# Projeto_Lora.net
KiCad netlist of a schematic drawn in EAGLE
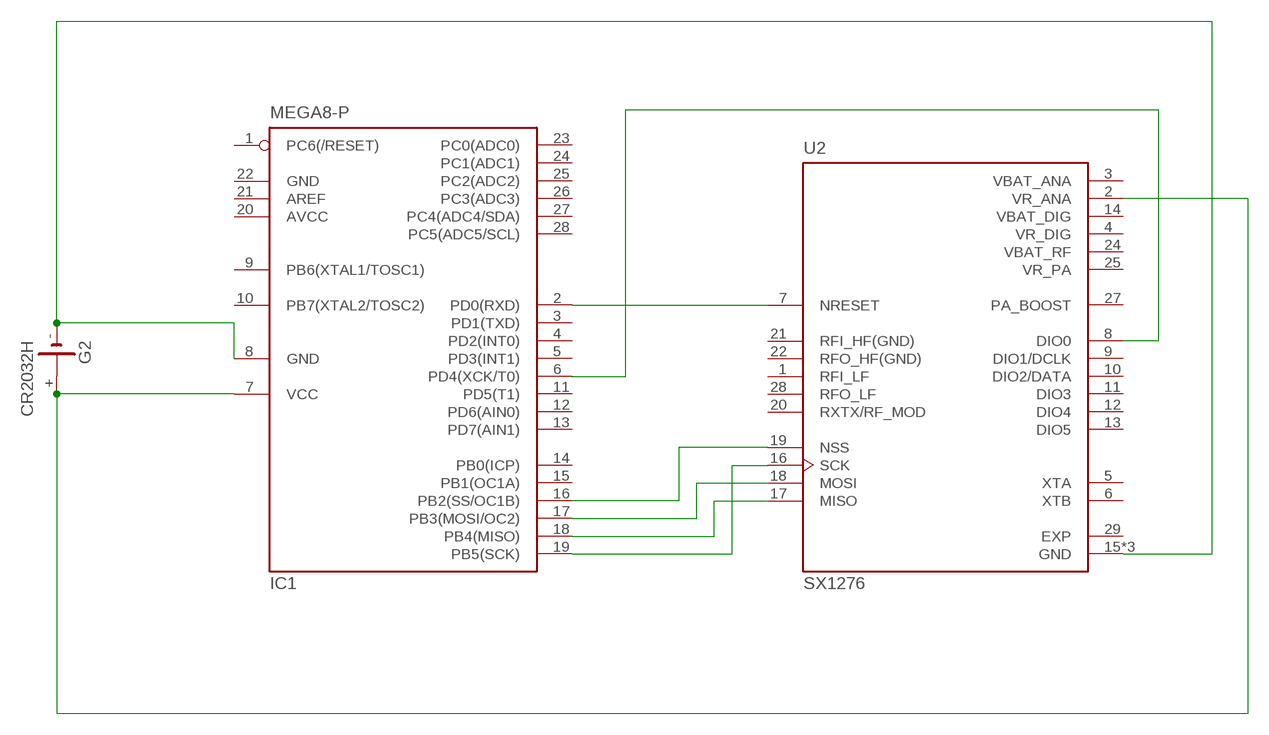
[diagram p0: schematic, sheet 1]

(export (version "E")
  (design (tool "Eeschema 10.0.6"))
  (components
    (comp (ref "G2")
      (value "CR2032H")
      (footprint "eagle-import:CR2032H")
      (libsource (lib "eagle-import") (part "CR2032H"))
    )
    (comp (ref "IC1")
      (value "MEGA8-P")
      (footprint "eagle-import:DIL28-3")
      (libsource (lib "eagle-import") (part "MEGA8-P"))
    )
    (comp (ref "U2")
      (value "SX1276")
      (footprint "eagle-import:QFN65P600X600X100-29N")
      (fields (field (name "MF") "Semtech Corporation"))
      (libsource (lib "eagle-import") (part "SX1276"))
    )
  )
  (nets
    (net (code "1") (name "/AVCC") (class "Default")
      (node (ref "IC1") (pin "20") (pinfunction "AVCC_20") (pintype "power_in"))
    )
    (net (code "2") (name "/EXP") (class "Default")
      (node (ref "U2") (pin "29") (pinfunction "EXP_29") (pintype "power_in"))
    )
    (net (code "3") (name "/GND") (class "Default")
      (node (ref "IC1") (pin "22") (pinfunction "GND_22") (pintype "power_in"))
    )
    (net (code "4") (name "/VBAT_ANA") (class "Default")
      (node (ref "U2") (pin "3") (pinfunction "VBAT_ANA_3") (pintype "power_in"))
    )
    (net (code "5") (name "/VBAT_DIG") (class "Default")
      (node (ref "U2") (pin "14") (pinfunction "VBAT_DIG_14") (pintype "power_in"))
    )
    (net (code "6") (name "/VBAT_RF") (class "Default")
      (node (ref "U2") (pin "24") (pinfunction "VBAT_RF_24") (pintype "power_in"))
    )
    (net (code "7") (name "/VR_DIG") (class "Default")
      (node (ref "U2") (pin "4") (pinfunction "VR_DIG_4") (pintype "power_in"))
    )
    (net (code "8") (name "/VR_PA") (class "Default")
      (node (ref "U2") (pin "25") (pinfunction "VR_PA_25") (pintype "power_in"))
    )
    (net (code "9") (name "Net-(G2-Pad-)") (class "Default")
      (node (ref "G2") (pin "-") (pinfunction "-_-") (pintype "passive"))
      (node (ref "IC1") (pin "8") (pinfunction "GND_8") (pintype "power_in"))
      (node (ref "U2") (pin "15") (pinfunction "GND_15") (pintype "power_in"))
      (node (ref "U2") (pin "23") (pinfunction "GND_23") (pintype "power_in"))
      (node (ref "U2") (pin "26") (pinfunction "GND_26") (pintype "power_in"))
    )
    (net (code "10") (name "Net-(IC1-PB2(SS{slash}OC1B))") (class "Default")
      (node (ref "IC1") (pin "16") (pinfunction "PB2(SS/OC1B)_16") (pintype "bidirectional"))
      (node (ref "U2") (pin "19") (pinfunction "NSS_19") (pintype "input"))
    )
    (net (code "11") (name "Net-(IC1-PB3(MOSI{slash}OC2))") (class "Default")
      (node (ref "IC1") (pin "17") (pinfunction "PB3(MOSI/OC2)_17") (pintype "bidirectional"))
      (node (ref "U2") (pin "18") (pinfunction "MOSI_18") (pintype "input"))
    )
    (net (code "12") (name "Net-(IC1-PB4(MISO))") (class "Default")
      (node (ref "IC1") (pin "18") (pinfunction "PB4(MISO)_18") (pintype "bidirectional"))
      (node (ref "U2") (pin "17") (pinfunction "MISO_17") (pintype "output"))
    )
    (net (code "13") (name "Net-(IC1-PB5(SCK))") (class "Default")
      (node (ref "IC1") (pin "19") (pinfunction "PB5(SCK)_19") (pintype "bidirectional"))
      (node (ref "U2") (pin "16") (pinfunction "SCK_16") (pintype "input"))
    )
    (net (code "14") (name "Net-(IC1-PD0(RXD))") (class "Default")
      (node (ref "IC1") (pin "2") (pinfunction "PD0(RXD)_2") (pintype "bidirectional"))
      (node (ref "U2") (pin "7") (pinfunction "NRESET_7") (pintype "bidirectional"))
    )
    (net (code "15") (name "Net-(IC1-PD4(XCK{slash}T0))") (class "Default")
      (node (ref "IC1") (pin "6") (pinfunction "PD4(XCK/T0)_6") (pintype "bidirectional"))
      (node (ref "U2") (pin "8") (pinfunction "DIO0_8") (pintype "bidirectional"))
    )
    (net (code "16") (name "Net-(IC1-VCC)") (class "Default")
      (node (ref "G2") (pin "+") (pinfunction "+_+") (pintype "passive"))
      (node (ref "IC1") (pin "7") (pinfunction "VCC_7") (pintype "power_in"))
      (node (ref "U2") (pin "2") (pinfunction "VR_ANA_2") (pintype "power_in"))
    )
    (net (code "17") (name "unconnected-(G2-+-Pad+@1)") (class "Default")
      (node (ref "G2") (pin "+@1") (pinfunction "+_+@1") (pintype "passive"))
    )
    (net (code "18") (name "unconnected-(IC1-AREF-Pad21)") (class "Default")
      (node (ref "IC1") (pin "21") (pinfunction "AREF_21") (pintype "passive"))
    )
    (net (code "19") (name "unconnected-(IC1-PB0(ICP)-Pad14)") (class "Default")
      (node (ref "IC1") (pin "14") (pinfunction "PB0(ICP)_14") (pintype "bidirectional"))
    )
    (net (code "20") (name "unconnected-(IC1-PB1(OC1A)-Pad15)") (class "Default")
      (node (ref "IC1") (pin "15") (pinfunction "PB1(OC1A)_15") (pintype "bidirectional"))
    )
    (net (code "21") (name "unconnected-(IC1-PB6(XTAL1{slash}TOSC1)-Pad9)") (class "Default")
      (node (ref "IC1") (pin "9") (pinfunction "PB6(XTAL1/TOSC1)_9") (pintype "bidirectional"))
    )
    (net (code "22") (name "unconnected-(IC1-PB7(XTAL2{slash}TOSC2)-Pad10)") (class "Default")
      (node (ref "IC1") (pin "10") (pinfunction "PB7(XTAL2/TOSC2)_10") (pintype "bidirectional"))
    )
    (net (code "23") (name "unconnected-(IC1-PC0(ADC0)-Pad23)") (class "Default")
      (node (ref "IC1") (pin "23") (pinfunction "PC0(ADC0)_23") (pintype "bidirectional"))
    )
    (net (code "24") (name "unconnected-(IC1-PC1(ADC1)-Pad24)") (class "Default")
      (node (ref "IC1") (pin "24") (pinfunction "PC1(ADC1)_24") (pintype "bidirectional"))
    )
    (net (code "25") (name "unconnected-(IC1-PC2(ADC2)-Pad25)") (class "Default")
      (node (ref "IC1") (pin "25") (pinfunction "PC2(ADC2)_25") (pintype "bidirectional"))
    )
    (net (code "26") (name "unconnected-(IC1-PC3(ADC3)-Pad26)") (class "Default")
      (node (ref "IC1") (pin "26") (pinfunction "PC3(ADC3)_26") (pintype "bidirectional"))
    )
    (net (code "27") (name "unconnected-(IC1-PC4(ADC4{slash}SDA)-Pad27)") (class "Default")
      (node (ref "IC1") (pin "27") (pinfunction "PC4(ADC4/SDA)_27") (pintype "bidirectional"))
    )
    (net (code "28") (name "unconnected-(IC1-PC5(ADC5{slash}SCL)-Pad28)") (class "Default")
      (node (ref "IC1") (pin "28") (pinfunction "PC5(ADC5/SCL)_28") (pintype "bidirectional"))
    )
    (net (code "29") (name "unconnected-(IC1-PC6({slash}RESET)-Pad1)") (class "Default")
      (node (ref "IC1") (pin "1") (pinfunction "PC6(/RESET)_1") (pintype "bidirectional"))
    )
    (net (code "30") (name "unconnected-(IC1-PD1(TXD)-Pad3)") (class "Default")
      (node (ref "IC1") (pin "3") (pinfunction "PD1(TXD)_3") (pintype "bidirectional"))
    )
    (net (code "31") (name "unconnected-(IC1-PD2(INT0)-Pad4)") (class "Default")
      (node (ref "IC1") (pin "4") (pinfunction "PD2(INT0)_4") (pintype "bidirectional"))
    )
    (net (code "32") (name "unconnected-(IC1-PD3(INT1)-Pad5)") (class "Default")
      (node (ref "IC1") (pin "5") (pinfunction "PD3(INT1)_5") (pintype "bidirectional"))
    )
    (net (code "33") (name "unconnected-(IC1-PD5(T1)-Pad11)") (class "Default")
      (node (ref "IC1") (pin "11") (pinfunction "PD5(T1)_11") (pintype "bidirectional"))
    )
    (net (code "34") (name "unconnected-(IC1-PD6(AIN0)-Pad12)") (class "Default")
      (node (ref "IC1") (pin "12") (pinfunction "PD6(AIN0)_12") (pintype "bidirectional"))
    )
    (net (code "35") (name "unconnected-(IC1-PD7(AIN1)-Pad13)") (class "Default")
      (node (ref "IC1") (pin "13") (pinfunction "PD7(AIN1)_13") (pintype "bidirectional"))
    )
    (net (code "36") (name "unconnected-(U2-DIO1{slash}DCLK-Pad9)") (class "Default")
      (node (ref "U2") (pin "9") (pinfunction "DIO1/DCLK_9") (pintype "bidirectional"))
    )
    (net (code "37") (name "unconnected-(U2-DIO2{slash}DATA-Pad10)") (class "Default")
      (node (ref "U2") (pin "10") (pinfunction "DIO2/DATA_10") (pintype "bidirectional"))
    )
    (net (code "38") (name "unconnected-(U2-DIO3-Pad11)") (class "Default")
      (node (ref "U2") (pin "11") (pinfunction "DIO3_11") (pintype "bidirectional"))
    )
    (net (code "39") (name "unconnected-(U2-DIO4-Pad12)") (class "Default")
      (node (ref "U2") (pin "12") (pinfunction "DIO4_12") (pintype "bidirectional"))
    )
    (net (code "40") (name "unconnected-(U2-DIO5-Pad13)") (class "Default")
      (node (ref "U2") (pin "13") (pinfunction "DIO5_13") (pintype "bidirectional"))
    )
    (net (code "41") (name "unconnected-(U2-PA_BOOST-Pad27)") (class "Default")
      (node (ref "U2") (pin "27") (pinfunction "PA_BOOST_27") (pintype "output"))
    )
    (net (code "42") (name "unconnected-(U2-RFI_HF(GND)-Pad21)") (class "Default")
      (node (ref "U2") (pin "21") (pinfunction "RFI_HF(GND)_21") (pintype "input"))
    )
    (net (code "43") (name "unconnected-(U2-RFI_LF-Pad1)") (class "Default")
      (node (ref "U2") (pin "1") (pinfunction "RFI_LF_1") (pintype "input"))
    )
    (net (code "44") (name "unconnected-(U2-RFO_HF(GND)-Pad22)") (class "Default")
      (node (ref "U2") (pin "22") (pinfunction "RFO_HF(GND)_22") (pintype "output"))
    )
    (net (code "45") (name "unconnected-(U2-RFO_LF-Pad28)") (class "Default")
      (node (ref "U2") (pin "28") (pinfunction "RFO_LF_28") (pintype "output"))
    )
    (net (code "46") (name "unconnected-(U2-RXTX{slash}RF_MOD-Pad20)") (class "Default")
      (node (ref "U2") (pin "20") (pinfunction "RXTX/RF_MOD_20") (pintype "output"))
    )
    (net (code "47") (name "unconnected-(U2-XTA-Pad5)") (class "Default")
      (node (ref "U2") (pin "5") (pinfunction "XTA_5") (pintype "bidirectional"))
    )
    (net (code "48") (name "unconnected-(U2-XTB-Pad6)") (class "Default")
      (node (ref "U2") (pin "6") (pinfunction "XTB_6") (pintype "bidirectional"))
    )
  )
)
